# MCU.net
KiCad netlist of a schematic drawn in Altium Designer
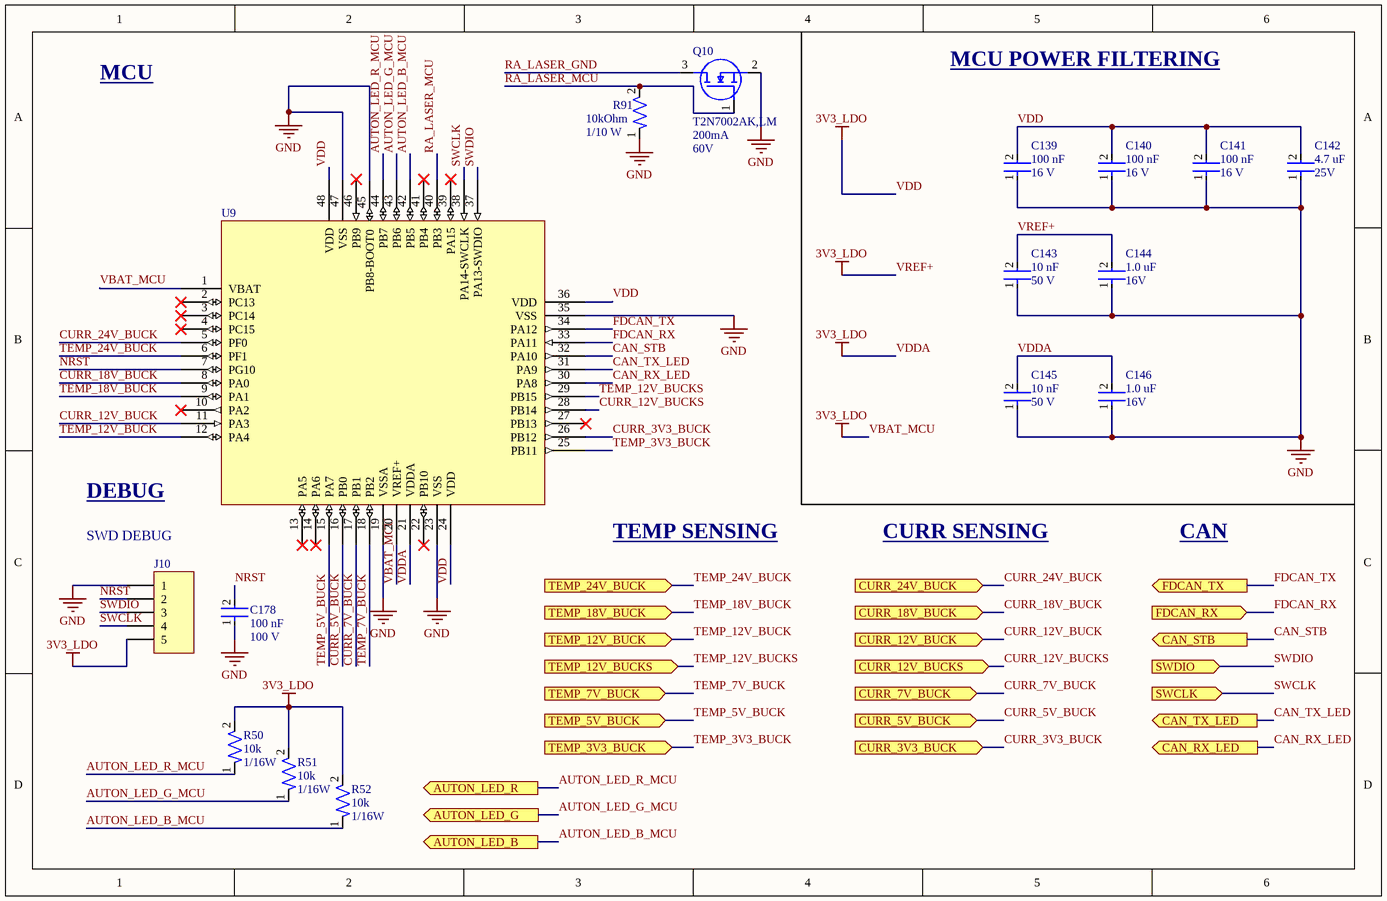
[diagram p0: MCU.SchDoc]

(export (version "E")
  (design (tool "Eeschema 10.0.6"))
  (components
    (comp (ref "C139")
      (value "CC0402KRX7R7BB104")
      (footprint "CAP-0402")
      (description "CAP CER 0.1UF 16V X7R 0402")
      (fields (field (name "VOLTAGE RATING") "16 V") (field (name "CAPACITANCE") "100 nF"))
      (libsource (lib "JLC_25") (part "CAP-0.1U-0001"))
    )
    (comp (ref "C140")
      (value "CC0402KRX7R7BB104")
      (footprint "CAP-0402")
      (description "CAP CER 0.1UF 16V X7R 0402")
      (fields (field (name "VOLTAGE RATING") "16 V") (field (name "CAPACITANCE") "100 nF"))
      (libsource (lib "JLC_25") (part "CAP-0.1U-0001"))
    )
    (comp (ref "C141")
      (value "CC0402KRX7R7BB104")
      (footprint "CAP-0402")
      (description "CAP CER 0.1UF 16V X7R 0402")
      (fields (field (name "VOLTAGE RATING") "16 V") (field (name "CAPACITANCE") "100 nF"))
      (libsource (lib "JLC_25") (part "CAP-0.1U-0001"))
    )
    (comp (ref "C142")
      (value "CC0603KRX5R8BB475")
      (footprint "CAP-0603")
      (description "CAP CER 4.7UF 25V X5R 0603")
      (fields (field (name "CAPACITANCE") "4.7 uF") (field (name "VOLTAGE") "25V"))
      (libsource (lib "JLC_25") (part "CAP-4.7U-0001"))
    )
    (comp (ref "C143")
      (value "CC0603KPX7R9BB103")
      (footprint "CAP-0603")
      (description "CAP CER 10000PF 50V X7R 0603")
      (fields (field (name "VOLTAGE") "50 V") (field (name "CAPACITANCE") "10 nF"))
      (libsource (lib "JLC_25") (part "CAP-10N-0002"))
    )
    (comp (ref "C144")
      (value "CC0603KRX7R7BB105")
      (footprint "CAP-0603")
      (description "CAP CER 1UF 16V X7R 0603")
      (fields (field (name "CAPACITANCE") "1.0 uF") (field (name "VOLTAGE") "16V"))
      (libsource (lib "JLC_25") (part "CAP-1U-0002"))
    )
    (comp (ref "C145")
      (value "CC0603KPX7R9BB103")
      (footprint "CAP-0603")
      (description "CAP CER 10000PF 50V X7R 0603")
      (fields (field (name "VOLTAGE") "50 V") (field (name "CAPACITANCE") "10 nF"))
      (libsource (lib "JLC_25") (part "CAP-10N-0002"))
    )
    (comp (ref "C146")
      (value "CC0603KRX7R7BB105")
      (footprint "CAP-0603")
      (description "CAP CER 1UF 16V X7R 0603")
      (fields (field (name "CAPACITANCE") "1.0 uF") (field (name "VOLTAGE") "16V"))
      (libsource (lib "JLC_25") (part "CAP-1U-0002"))
    )
    (comp (ref "C178")
      (value "CC0603KRX7R0BB104")
      (footprint "CAP-0603")
      (description "CAP CER 0.1UF 100V X7R 0603")
      (fields (field (name "CAPACITANCE") "100 nF") (field (name "VOLTAGE") "100 V"))
      (libsource (lib "JLC_25") (part "CAP-100N-0001"))
    )
    (comp (ref "J10")
      (value "Header 5")
      (footprint "HDR1X5")
      (description "Header, 5-Pin")
      (fields (field (name "PUBLISHER") "Altium Limited"))
      (libsource (lib "Miscellaneous Connectors") (part "Header 5"))
    )
    (comp (ref "Q10")
      (value "T2N7002AK,LM")
      (footprint "NMOS-SOT23-3")
      (description "MOSFET N-CH 60V 200MA SOT23")
      (fields
        (field (name "MANUFACTURER") "Toshiba")
        (field (name "ID-CONTINUOUS") "200mA")
        (field (name "VDS-MAX") "60V")
      )
      (libsource (lib "MasterLib") (part "NMOS-200MA-0001"))
    )
    (comp (ref "R50")
      (value "RC0402FR-0710KL")
      (footprint "RES-0402")
      (description "RES 10K OHM 1% 1/16W 0402")
      (fields
        (field (name "TOLERANCE") "1%")
        (field (name "RESISTANCE") "10k")
        (field (name "POWER") "1/16W")
      )
      (libsource (lib "JLC_25") (part "RES-10k-0001"))
    )
    (comp (ref "R51")
      (value "RC0402FR-0710KL")
      (footprint "RES-0402")
      (description "RES 10K OHM 1% 1/16W 0402")
      (fields
        (field (name "TOLERANCE") "1%")
        (field (name "RESISTANCE") "10k")
        (field (name "POWER") "1/16W")
      )
      (libsource (lib "JLC_25") (part "RES-10k-0001"))
    )
    (comp (ref "R52")
      (value "RC0402FR-0710KL")
      (footprint "RES-0402")
      (description "RES 10K OHM 1% 1/16W 0402")
      (fields
        (field (name "TOLERANCE") "1%")
        (field (name "RESISTANCE") "10k")
        (field (name "POWER") "1/16W")
      )
      (libsource (lib "JLC_25") (part "RES-10k-0001"))
    )
    (comp (ref "R91")
      (value "RMCF0603ZT0R00")
      (footprint "RES-0603")
      (description "0 Ohms Jumper 0.1W, 1/10W Chip Resistor 0603 (1608 Metric) Automotive AEC-Q200 Thick Film")
      (fields (field (name "RESISTANCE") "10kOhm") (field (name "POWER") "1/10 W"))
      (libsource (lib "MasterLib") (part "RES-0-0001"))
    )
    (comp (ref "U9")
      (value "STM32G431CBT6")
      (footprint "IC-LQFP48")
      (description "IC MCU 32BIT 128KB FLASH 48LQFP")
      (libsource (lib "JLC_25") (part "IC-STM32G431CBT6"))
    )
  )
  (nets
    (net (code "1") (name "/AUTON_LED_B_MCU") (class "Default")
      (node (ref "R52") (pin "1") (pinfunction "1_1") (pintype "passive"))
      (node (ref "U9") (pin "42") (pinfunction "PB5_42") (pintype "bidirectional"))
    )
    (net (code "2") (name "/AUTON_LED_G_MCU") (class "Default")
      (node (ref "R51") (pin "1") (pinfunction "1_1") (pintype "passive"))
      (node (ref "U9") (pin "43") (pinfunction "PB6_43") (pintype "bidirectional"))
    )
    (net (code "3") (name "/AUTON_LED_R_MCU") (class "Default")
      (node (ref "R50") (pin "1") (pinfunction "1_1") (pintype "passive"))
      (node (ref "U9") (pin "44") (pinfunction "PB7_44") (pintype "bidirectional"))
    )
    (net (code "4") (name "/CAN_RX_LED") (class "Default")
      (node (ref "U9") (pin "30") (pinfunction "PA8_30") (pintype "output"))
    )
    (net (code "5") (name "/CAN_STB") (class "Default")
      (node (ref "U9") (pin "32") (pinfunction "PA10_32") (pintype "output"))
    )
    (net (code "6") (name "/CAN_TX_LED") (class "Default")
      (node (ref "U9") (pin "31") (pinfunction "PA9_31") (pintype "output"))
    )
    (net (code "7") (name "/CURR_3V3_BUCK") (class "Default")
      (node (ref "U9") (pin "26") (pinfunction "PB12_26") (pintype "output"))
    )
    (net (code "8") (name "/CURR_5V_BUCK") (class "Default")
      (node (ref "U9") (pin "16") (pinfunction "PB0_16") (pintype "bidirectional"))
    )
    (net (code "9") (name "/CURR_7V_BUCK") (class "Default")
      (node (ref "U9") (pin "17") (pinfunction "PB1_17") (pintype "bidirectional"))
    )
    (net (code "10") (name "/CURR_12V_BUCK") (class "Default")
      (node (ref "U9") (pin "11") (pinfunction "PA3_11") (pintype "input"))
    )
    (net (code "11") (name "/CURR_12V_BUCKS") (class "Default")
      (node (ref "U9") (pin "28") (pinfunction "PB14_28") (pintype "output"))
    )
    (net (code "12") (name "/CURR_18V_BUCK") (class "Default")
      (node (ref "U9") (pin "8") (pinfunction "PA0_8") (pintype "bidirectional"))
    )
    (net (code "13") (name "/CURR_24V_BUCK") (class "Default")
      (node (ref "U9") (pin "5") (pinfunction "PF0_5") (pintype "bidirectional"))
    )
    (net (code "14") (name "/FDCAN_RX") (class "Default")
      (node (ref "U9") (pin "33") (pinfunction "PA11_33") (pintype "input"))
    )
    (net (code "15") (name "/FDCAN_TX") (class "Default")
      (node (ref "U9") (pin "34") (pinfunction "PA12_34") (pintype "output"))
    )
    (net (code "16") (name "/NRST") (class "Default")
      (node (ref "C178") (pin "2") (pinfunction "2_2") (pintype "passive"))
      (node (ref "J10") (pin "2") (pinfunction "2_2") (pintype "passive"))
      (node (ref "U9") (pin "7") (pinfunction "PG10_7") (pintype "bidirectional"))
    )
    (net (code "17") (name "/RA_LASER_GND") (class "Default")
      (node (ref "Q10") (pin "3") (pinfunction "D_3") (pintype "passive"))
    )
    (net (code "18") (name "/RA_LASER_MCU") (class "Default")
      (node (ref "Q10") (pin "1") (pinfunction "G_1") (pintype "passive"))
      (node (ref "R91") (pin "2") (pinfunction "2_2") (pintype "passive"))
      (node (ref "U9") (pin "40") (pinfunction "PB3_40") (pintype "bidirectional"))
    )
    (net (code "19") (name "/SWCLK") (class "Default")
      (node (ref "J10") (pin "4") (pinfunction "4_4") (pintype "passive"))
      (node (ref "U9") (pin "38") (pinfunction "PA14-SWCLK_38") (pintype "input"))
    )
    (net (code "20") (name "/SWDIO") (class "Default")
      (node (ref "J10") (pin "3") (pinfunction "3_3") (pintype "passive"))
      (node (ref "U9") (pin "37") (pinfunction "PA13-SWDIO_37") (pintype "input"))
    )
    (net (code "21") (name "/TEMP_3V3_BUCK") (class "Default")
      (node (ref "U9") (pin "25") (pinfunction "PB11_25") (pintype "output"))
    )
    (net (code "22") (name "/TEMP_5V_BUCK") (class "Default")
      (node (ref "U9") (pin "15") (pinfunction "PA7_15") (pintype "bidirectional"))
    )
    (net (code "23") (name "/TEMP_7V_BUCK") (class "Default")
      (node (ref "U9") (pin "18") (pinfunction "PB2_18") (pintype "bidirectional"))
    )
    (net (code "24") (name "/TEMP_12V_BUCK") (class "Default")
      (node (ref "U9") (pin "12") (pinfunction "PA4_12") (pintype "bidirectional"))
    )
    (net (code "25") (name "/TEMP_12V_BUCKS") (class "Default")
      (node (ref "U9") (pin "29") (pinfunction "PB15_29") (pintype "output"))
    )
    (net (code "26") (name "/TEMP_18V_BUCK") (class "Default")
      (node (ref "U9") (pin "9") (pinfunction "PA1_9") (pintype "bidirectional"))
    )
    (net (code "27") (name "/TEMP_24V_BUCK") (class "Default")
      (node (ref "U9") (pin "6") (pinfunction "PF1_6") (pintype "bidirectional"))
    )
    (net (code "28") (name "3V3_LDO") (class "Default")
      (node (ref "C139") (pin "2") (pinfunction "2_2") (pintype "passive"))
      (node (ref "C140") (pin "2") (pinfunction "2_2") (pintype "passive"))
      (node (ref "C141") (pin "2") (pinfunction "2_2") (pintype "passive"))
      (node (ref "C142") (pin "2") (pinfunction "2_2") (pintype "passive"))
      (node (ref "C143") (pin "2") (pinfunction "2_2") (pintype "passive"))
      (node (ref "C144") (pin "2") (pinfunction "2_2") (pintype "passive"))
      (node (ref "C145") (pin "2") (pinfunction "2_2") (pintype "passive"))
      (node (ref "C146") (pin "2") (pinfunction "2_2") (pintype "passive"))
      (node (ref "J10") (pin "5") (pinfunction "5_5") (pintype "passive"))
      (node (ref "R50") (pin "2") (pinfunction "2_2") (pintype "passive"))
      (node (ref "R51") (pin "2") (pinfunction "2_2") (pintype "passive"))
      (node (ref "R52") (pin "2") (pinfunction "2_2") (pintype "passive"))
      (node (ref "U9") (pin "1") (pinfunction "VBAT_1") (pintype "power_in"))
      (node (ref "U9") (pin "20") (pinfunction "VREF+_20") (pintype "power_in"))
      (node (ref "U9") (pin "21") (pinfunction "VDDA_21") (pintype "power_in"))
      (node (ref "U9") (pin "24") (pinfunction "VDD_24") (pintype "power_in"))
      (node (ref "U9") (pin "36") (pinfunction "VDD_36") (pintype "power_in"))
      (node (ref "U9") (pin "48") (pinfunction "VDD_48") (pintype "power_in"))
    )
    (net (code "29") (name "GND") (class "Default")
      (node (ref "C139") (pin "1") (pinfunction "1_1") (pintype "passive"))
      (node (ref "C140") (pin "1") (pinfunction "1_1") (pintype "passive"))
      (node (ref "C141") (pin "1") (pinfunction "1_1") (pintype "passive"))
      (node (ref "C142") (pin "1") (pinfunction "1_1") (pintype "passive"))
      (node (ref "C143") (pin "1") (pinfunction "1_1") (pintype "passive"))
      (node (ref "C144") (pin "1") (pinfunction "1_1") (pintype "passive"))
      (node (ref "C145") (pin "1") (pinfunction "1_1") (pintype "passive"))
      (node (ref "C146") (pin "1") (pinfunction "1_1") (pintype "passive"))
      (node (ref "C178") (pin "1") (pinfunction "1_1") (pintype "passive"))
      (node (ref "J10") (pin "1") (pinfunction "1_1") (pintype "passive"))
      (node (ref "Q10") (pin "2") (pinfunction "S_2") (pintype "passive"))
      (node (ref "R91") (pin "1") (pinfunction "1_1") (pintype "passive"))
      (node (ref "U9") (pin "19") (pinfunction "VSSA_19") (pintype "power_in"))
      (node (ref "U9") (pin "23") (pinfunction "VSS_23") (pintype "power_in"))
      (node (ref "U9") (pin "35") (pinfunction "VSS_35") (pintype "power_in"))
      (node (ref "U9") (pin "45") (pinfunction "PB8-BOOT0_45") (pintype "bidirectional"))
      (node (ref "U9") (pin "47") (pinfunction "VSS_47") (pintype "power_in"))
    )
    (net (code "30") (name "unconnected-(U9-PA2-Pad10)") (class "Default")
      (node (ref "U9") (pin "10") (pinfunction "PA2_10") (pintype "output+no_connect"))
    )
    (net (code "31") (name "unconnected-(U9-PA5-Pad13)") (class "Default")
      (node (ref "U9") (pin "13") (pinfunction "PA5_13") (pintype "bidirectional+no_connect"))
    )
    (net (code "32") (name "unconnected-(U9-PA6-Pad14)") (class "Default")
      (node (ref "U9") (pin "14") (pinfunction "PA6_14") (pintype "bidirectional+no_connect"))
    )
    (net (code "33") (name "unconnected-(U9-PA15-Pad39)") (class "Default")
      (node (ref "U9") (pin "39") (pinfunction "PA15_39") (pintype "bidirectional+no_connect"))
    )
    (net (code "34") (name "unconnected-(U9-PB4-Pad41)") (class "Default")
      (node (ref "U9") (pin "41") (pinfunction "PB4_41") (pintype "bidirectional+no_connect"))
    )
    (net (code "35") (name "unconnected-(U9-PB9-Pad46)") (class "Default")
      (node (ref "U9") (pin "46") (pinfunction "PB9_46") (pintype "input+no_connect"))
    )
    (net (code "36") (name "unconnected-(U9-PB10-Pad22)") (class "Default")
      (node (ref "U9") (pin "22") (pinfunction "PB10_22") (pintype "bidirectional+no_connect"))
    )
    (net (code "37") (name "unconnected-(U9-PB13-Pad27)") (class "Default")
      (node (ref "U9") (pin "27") (pinfunction "PB13_27") (pintype "output+no_connect"))
    )
    (net (code "38") (name "unconnected-(U9-PC13-Pad2)") (class "Default")
      (node (ref "U9") (pin "2") (pinfunction "PC13_2") (pintype "bidirectional+no_connect"))
    )
    (net (code "39") (name "unconnected-(U9-PC14-Pad3)") (class "Default")
      (node (ref "U9") (pin "3") (pinfunction "PC14_3") (pintype "bidirectional+no_connect"))
    )
    (net (code "40") (name "unconnected-(U9-PC15-Pad4)") (class "Default")
      (node (ref "U9") (pin "4") (pinfunction "PC15_4") (pintype "bidirectional+no_connect"))
    )
  )
)
